# actik-retrofit.net
KiCad netlist of a schematic drawn in EAGLE
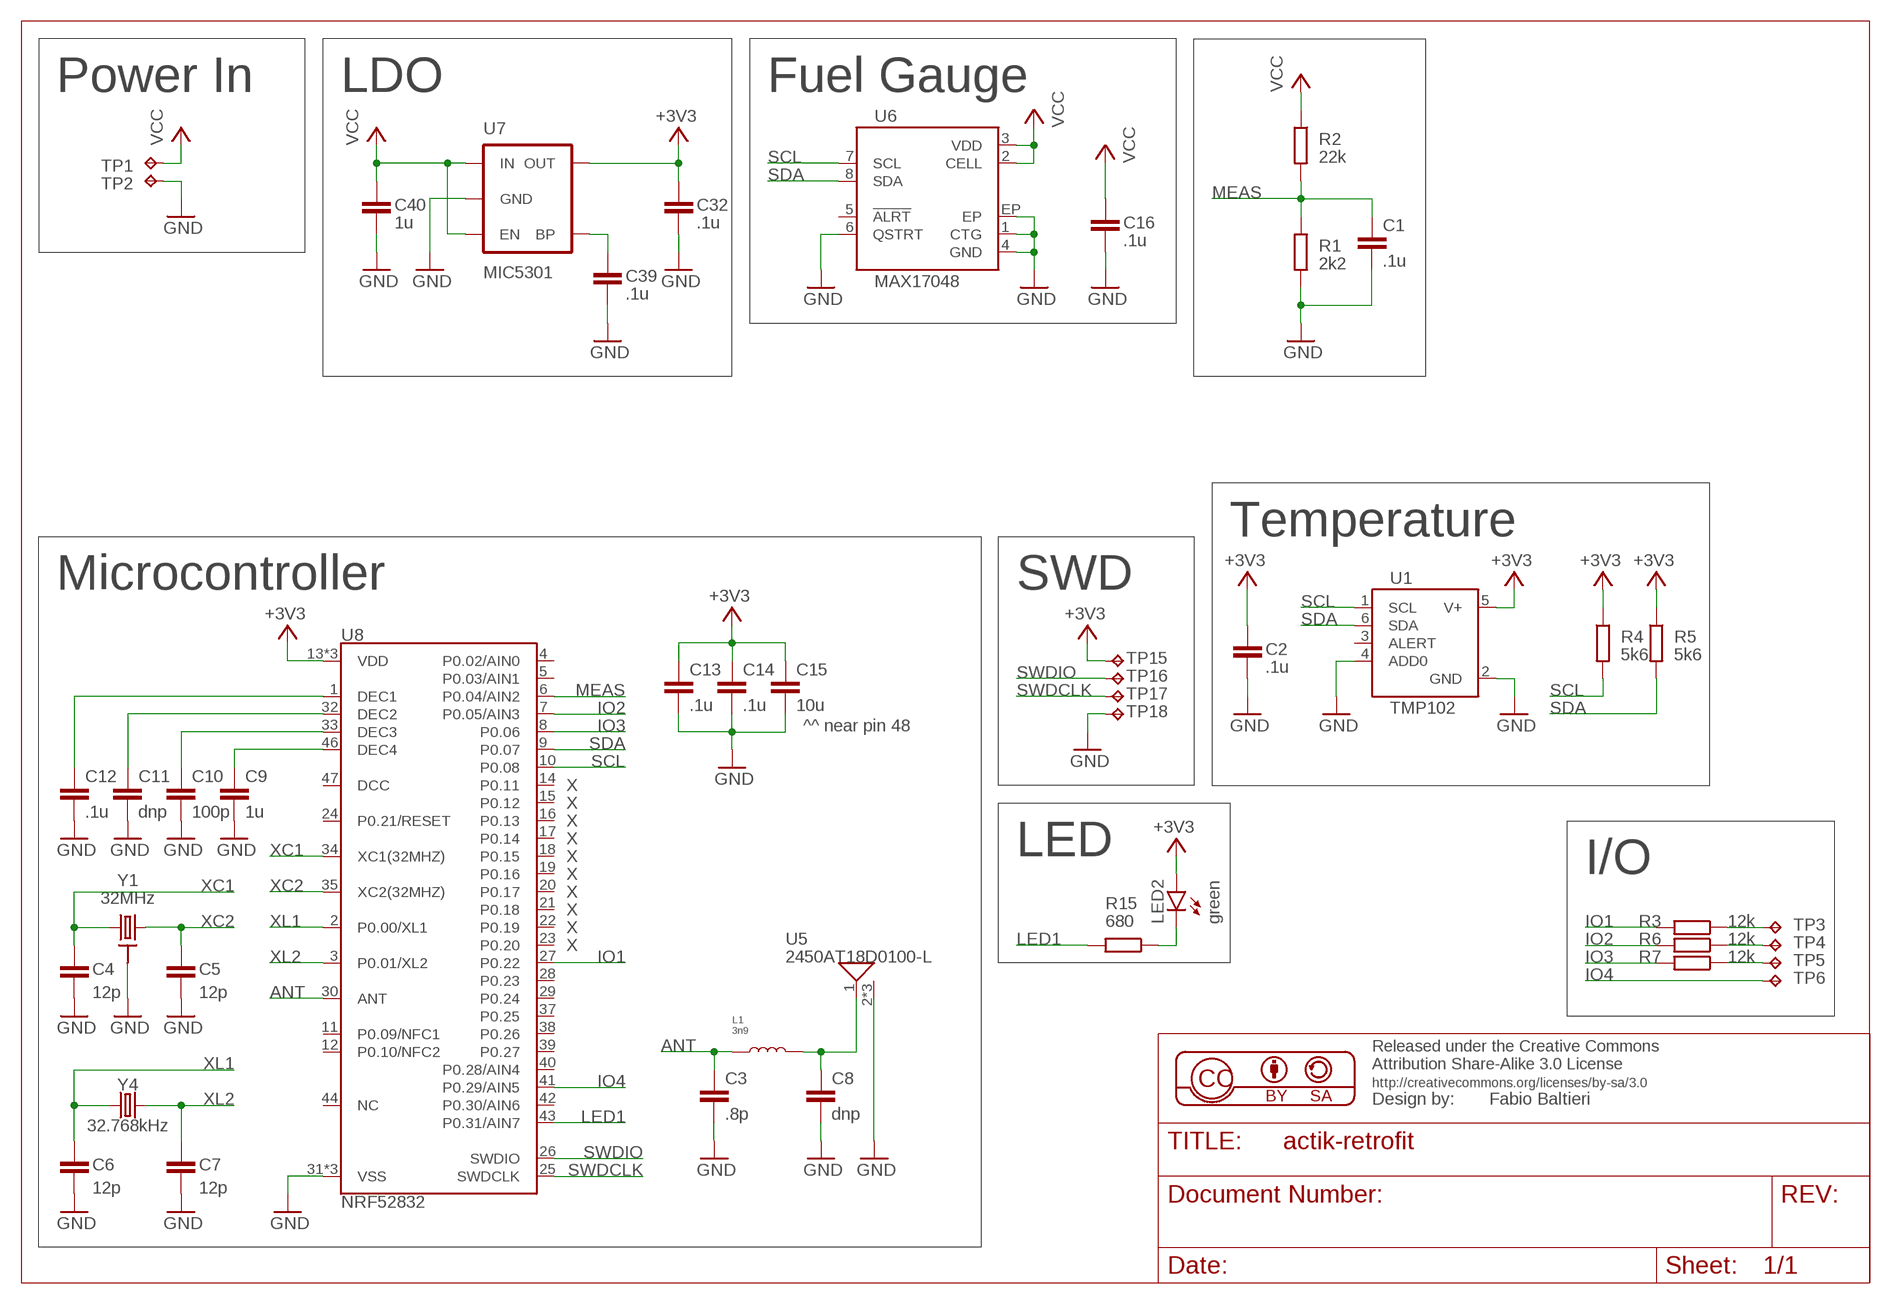
[diagram p0: schematic, sheet 1]

(export (version "E")
  (design (tool "Eeschema 10.0.6"))
  (components
    (comp (ref "C1")
      (value ".1u")
      (footprint "eagle-import:0603")
      (libsource (lib "eagle-import") (part "C0603"))
    )
    (comp (ref "C2")
      (value ".1u")
      (footprint "eagle-import:0603")
      (libsource (lib "eagle-import") (part "C0603"))
    )
    (comp (ref "C3")
      (value ".8p")
      (footprint "eagle-import:0603")
      (libsource (lib "eagle-import") (part "C0603"))
    )
    (comp (ref "C4")
      (value "12p")
      (footprint "eagle-import:0603")
      (libsource (lib "eagle-import") (part "C0603"))
    )
    (comp (ref "C5")
      (value "12p")
      (footprint "eagle-import:0603")
      (libsource (lib "eagle-import") (part "C0603"))
    )
    (comp (ref "C6")
      (value "12p")
      (footprint "eagle-import:0603")
      (libsource (lib "eagle-import") (part "C0603"))
    )
    (comp (ref "C7")
      (value "12p")
      (footprint "eagle-import:0603")
      (libsource (lib "eagle-import") (part "C0603"))
    )
    (comp (ref "C8")
      (value "dnp")
      (footprint "eagle-import:0603")
      (libsource (lib "eagle-import") (part "C0603"))
    )
    (comp (ref "C9")
      (value "1u")
      (footprint "eagle-import:0603")
      (libsource (lib "eagle-import") (part "C0603"))
    )
    (comp (ref "C10")
      (value "100p")
      (footprint "eagle-import:0603")
      (libsource (lib "eagle-import") (part "C0603"))
    )
    (comp (ref "C11")
      (value "dnp")
      (footprint "eagle-import:0603")
      (libsource (lib "eagle-import") (part "C0603"))
    )
    (comp (ref "C12")
      (value ".1u")
      (footprint "eagle-import:0603")
      (libsource (lib "eagle-import") (part "C0603"))
    )
    (comp (ref "C13")
      (value ".1u")
      (footprint "eagle-import:0603")
      (libsource (lib "eagle-import") (part "C0603"))
    )
    (comp (ref "C14")
      (value ".1u")
      (footprint "eagle-import:0603")
      (libsource (lib "eagle-import") (part "C0603"))
    )
    (comp (ref "C15")
      (value "10u")
      (footprint "eagle-import:0603")
      (libsource (lib "eagle-import") (part "C0603"))
    )
    (comp (ref "C16")
      (value ".1u")
      (footprint "eagle-import:0603")
      (libsource (lib "eagle-import") (part "C0603"))
    )
    (comp (ref "C32")
      (value ".1u")
      (footprint "eagle-import:0603")
      (libsource (lib "eagle-import") (part "C0603"))
    )
    (comp (ref "C39")
      (value ".1u")
      (footprint "eagle-import:0603")
      (libsource (lib "eagle-import") (part "C0603"))
    )
    (comp (ref "C40")
      (value "1u")
      (footprint "eagle-import:0603")
      (libsource (lib "eagle-import") (part "C0603"))
    )
    (comp (ref "L1")
      (value "3n9")
      (footprint "eagle-import:L0603")
      (libsource (lib "eagle-import") (part "INDUCTOR_0603"))
    )
    (comp (ref "LED2")
      (value "green")
      (footprint "eagle-import:SML0805")
      (libsource (lib "eagle-import") (part "LEDSML0805"))
    )
    (comp (ref "R1")
      (value "2k2")
      (footprint "eagle-import:0603")
      (libsource (lib "eagle-import") (part "R0603"))
    )
    (comp (ref "R2")
      (value "22k")
      (footprint "eagle-import:0603")
      (libsource (lib "eagle-import") (part "R0603"))
    )
    (comp (ref "R3")
      (value "12k")
      (footprint "eagle-import:0603")
      (libsource (lib "eagle-import") (part "R0603"))
    )
    (comp (ref "R4")
      (value "5k6")
      (footprint "eagle-import:0603")
      (libsource (lib "eagle-import") (part "R0603"))
    )
    (comp (ref "R5")
      (value "5k6")
      (footprint "eagle-import:0603")
      (libsource (lib "eagle-import") (part "R0603"))
    )
    (comp (ref "R6")
      (value "12k")
      (footprint "eagle-import:0603")
      (libsource (lib "eagle-import") (part "R0603"))
    )
    (comp (ref "R7")
      (value "12k")
      (footprint "eagle-import:0603")
      (libsource (lib "eagle-import") (part "R0603"))
    )
    (comp (ref "R15")
      (value "680")
      (footprint "eagle-import:0603")
      (libsource (lib "eagle-import") (part "R0603"))
    )
    (comp (ref "TP1")
      (value "TPTP10R")
      (footprint "eagle-import:TP10R")
      (libsource (lib "eagle-import") (part "TPTP10R"))
    )
    (comp (ref "TP2")
      (value "TPTP10R")
      (footprint "eagle-import:TP10R")
      (libsource (lib "eagle-import") (part "TPTP10R"))
    )
    (comp (ref "TP3")
      (value "TPTP10R")
      (footprint "eagle-import:TP10R")
      (libsource (lib "eagle-import") (part "TPTP10R"))
    )
    (comp (ref "TP4")
      (value "TPTP10R")
      (footprint "eagle-import:TP10R")
      (libsource (lib "eagle-import") (part "TPTP10R"))
    )
    (comp (ref "TP5")
      (value "TPTP10R")
      (footprint "eagle-import:TP10R")
      (libsource (lib "eagle-import") (part "TPTP10R"))
    )
    (comp (ref "TP6")
      (value "TPTP10R")
      (footprint "eagle-import:TP10R")
      (libsource (lib "eagle-import") (part "TPTP10R"))
    )
    (comp (ref "TP15")
      (value "TPTP10R")
      (footprint "eagle-import:TP10R")
      (libsource (lib "eagle-import") (part "TPTP10R"))
    )
    (comp (ref "TP16")
      (value "TPTP10R")
      (footprint "eagle-import:TP10R")
      (libsource (lib "eagle-import") (part "TPTP10R"))
    )
    (comp (ref "TP17")
      (value "TPTP10R")
      (footprint "eagle-import:TP10R")
      (libsource (lib "eagle-import") (part "TPTP10R"))
    )
    (comp (ref "TP18")
      (value "TPTP10R")
      (footprint "eagle-import:TP10R")
      (libsource (lib "eagle-import") (part "TPTP10R"))
    )
    (comp (ref "U1")
      (value "TMP102")
      (footprint "eagle-import:SOT563")
      (libsource (lib "eagle-import") (part "TMP102"))
    )
    (comp (ref "U5")
      (value "2450AT18D0100-L")
      (footprint "eagle-import:2450AT18D0100-L")
      (libsource (lib "eagle-import") (part "2450AT18D0100-L"))
    )
    (comp (ref "U6")
      (value "MAX17048")
      (footprint "eagle-import:TDFN8L")
      (libsource (lib "eagle-import") (part "MAX17048"))
    )
    (comp (ref "U7")
      (value "MIC5301")
      (footprint "eagle-import:SOT23-5")
      (libsource (lib "eagle-import") (part "V_REG_LDOSMD"))
    )
    (comp (ref "U8")
      (value "NRF52832")
      (footprint "eagle-import:QFN48-6X6MM")
      (libsource (lib "eagle-import") (part "NRF52832"))
    )
    (comp (ref "Y1")
      (value "32MHz")
      (footprint "eagle-import:XTAL-2X1.6")
      (libsource (lib "eagle-import") (part "XTAL-GND-2X1.6"))
    )
    (comp (ref "Y4")
      (value "32.768kHz")
      (footprint "eagle-import:CRYSTAL-SMD-3.2X1.5MM")
      (libsource (lib "eagle-import") (part "CRYSTAL-32.768KHZSMD-3.2X1.5"))
    )
  )
  (nets
    (net (code "1") (name "+3V3") (class "Default")
      (node (ref "C13") (pin "1") (pinfunction "1_1") (pintype "passive"))
      (node (ref "C14") (pin "1") (pinfunction "1_1") (pintype "passive"))
      (node (ref "C15") (pin "1") (pinfunction "1_1") (pintype "passive"))
      (node (ref "C2") (pin "1") (pinfunction "1_1") (pintype "passive"))
      (node (ref "C32") (pin "1") (pinfunction "1_1") (pintype "passive"))
      (node (ref "LED2") (pin "A") (pinfunction "A_A") (pintype "passive"))
      (node (ref "R4") (pin "1") (pinfunction "1_1") (pintype "passive"))
      (node (ref "R5") (pin "1") (pinfunction "1_1") (pintype "passive"))
      (node (ref "TP15") (pin "TP") (pinfunction "TP_TP") (pintype "input"))
      (node (ref "U1") (pin "5") (pinfunction "V+_5") (pintype "bidirectional"))
      (node (ref "U7") (pin "5") (pinfunction "OUT_5") (pintype "passive"))
      (node (ref "U8") (pin "13") (pinfunction "VDD_13") (pintype "bidirectional"))
      (node (ref "U8") (pin "36") (pinfunction "VDD_36") (pintype "bidirectional"))
      (node (ref "U8") (pin "48") (pinfunction "VDD_48") (pintype "bidirectional"))
    )
    (net (code "2") (name "/ANT") (class "Default")
      (node (ref "C3") (pin "1") (pinfunction "1_1") (pintype "passive"))
      (node (ref "L1") (pin "P$1") (pinfunction "P$1_P$1") (pintype "passive"))
      (node (ref "U8") (pin "30") (pinfunction "ANT_30") (pintype "bidirectional"))
    )
    (net (code "3") (name "/IO1") (class "Default")
      (node (ref "R3") (pin "2") (pinfunction "2_2") (pintype "passive"))
      (node (ref "U8") (pin "27") (pinfunction "P0.22_27") (pintype "bidirectional"))
    )
    (net (code "4") (name "/IO2") (class "Default")
      (node (ref "R6") (pin "2") (pinfunction "2_2") (pintype "passive"))
      (node (ref "U8") (pin "7") (pinfunction "P0.05/AIN3_7") (pintype "bidirectional"))
    )
    (net (code "5") (name "/IO3") (class "Default")
      (node (ref "R7") (pin "2") (pinfunction "2_2") (pintype "passive"))
      (node (ref "U8") (pin "8") (pinfunction "P0.06_8") (pintype "bidirectional"))
    )
    (net (code "6") (name "/IO4") (class "Default")
      (node (ref "TP6") (pin "TP") (pinfunction "TP_TP") (pintype "input"))
      (node (ref "U8") (pin "41") (pinfunction "P0.29/AIN5_41") (pintype "bidirectional"))
    )
    (net (code "7") (name "/LED1") (class "Default")
      (node (ref "R15") (pin "2") (pinfunction "2_2") (pintype "passive"))
      (node (ref "U8") (pin "43") (pinfunction "P0.31/AIN7_43") (pintype "bidirectional"))
    )
    (net (code "8") (name "/MEAS") (class "Default")
      (node (ref "C1") (pin "1") (pinfunction "1_1") (pintype "passive"))
      (node (ref "R1") (pin "1") (pinfunction "1_1") (pintype "passive"))
      (node (ref "R2") (pin "2") (pinfunction "2_2") (pintype "passive"))
      (node (ref "U8") (pin "6") (pinfunction "P0.04/AIN2_6") (pintype "bidirectional"))
    )
    (net (code "9") (name "/SCL") (class "Default")
      (node (ref "R4") (pin "2") (pinfunction "2_2") (pintype "passive"))
      (node (ref "U1") (pin "1") (pinfunction "SCL_1") (pintype "bidirectional"))
      (node (ref "U6") (pin "7") (pinfunction "SCL_7") (pintype "bidirectional"))
      (node (ref "U8") (pin "10") (pinfunction "P0.08_10") (pintype "bidirectional"))
    )
    (net (code "10") (name "/SDA") (class "Default")
      (node (ref "R5") (pin "2") (pinfunction "2_2") (pintype "passive"))
      (node (ref "U1") (pin "6") (pinfunction "SDA_6") (pintype "bidirectional"))
      (node (ref "U6") (pin "8") (pinfunction "SDA_8") (pintype "bidirectional"))
      (node (ref "U8") (pin "9") (pinfunction "P0.07_9") (pintype "bidirectional"))
    )
    (net (code "11") (name "/SWDCLK") (class "Default")
      (node (ref "TP17") (pin "TP") (pinfunction "TP_TP") (pintype "input"))
      (node (ref "U8") (pin "25") (pinfunction "SWDCLK_25") (pintype "bidirectional"))
    )
    (net (code "12") (name "/SWDIO") (class "Default")
      (node (ref "TP16") (pin "TP") (pinfunction "TP_TP") (pintype "input"))
      (node (ref "U8") (pin "26") (pinfunction "SWDIO_26") (pintype "bidirectional"))
    )
    (net (code "13") (name "/XC1") (class "Default")
      (node (ref "C4") (pin "1") (pinfunction "1_1") (pintype "passive"))
      (node (ref "U8") (pin "34") (pinfunction "XC1(32MHZ)_34") (pintype "bidirectional"))
      (node (ref "Y1") (pin "1") (pinfunction "1_1") (pintype "passive"))
    )
    (net (code "14") (name "/XC2") (class "Default")
      (node (ref "C5") (pin "1") (pinfunction "1_1") (pintype "passive"))
      (node (ref "U8") (pin "35") (pinfunction "XC2(32MHZ)_35") (pintype "bidirectional"))
      (node (ref "Y1") (pin "3") (pinfunction "2_3") (pintype "passive"))
    )
    (net (code "15") (name "/XL1") (class "Default")
      (node (ref "C6") (pin "1") (pinfunction "1_1") (pintype "passive"))
      (node (ref "U8") (pin "2") (pinfunction "P0.00/XL1_2") (pintype "bidirectional"))
      (node (ref "Y4") (pin "P$1") (pinfunction "1_P$1") (pintype "passive"))
    )
    (net (code "16") (name "/XL2") (class "Default")
      (node (ref "C7") (pin "1") (pinfunction "1_1") (pintype "passive"))
      (node (ref "U8") (pin "3") (pinfunction "P0.01/XL2_3") (pintype "bidirectional"))
      (node (ref "Y4") (pin "P$2") (pinfunction "2_P$2") (pintype "passive"))
    )
    (net (code "17") (name "GND") (class "Default")
      (node (ref "C1") (pin "2") (pinfunction "2_2") (pintype "passive"))
      (node (ref "C10") (pin "2") (pinfunction "2_2") (pintype "passive"))
      (node (ref "C11") (pin "2") (pinfunction "2_2") (pintype "passive"))
      (node (ref "C12") (pin "2") (pinfunction "2_2") (pintype "passive"))
      (node (ref "C13") (pin "2") (pinfunction "2_2") (pintype "passive"))
      (node (ref "C14") (pin "2") (pinfunction "2_2") (pintype "passive"))
      (node (ref "C15") (pin "2") (pinfunction "2_2") (pintype "passive"))
      (node (ref "C16") (pin "2") (pinfunction "2_2") (pintype "passive"))
      (node (ref "C2") (pin "2") (pinfunction "2_2") (pintype "passive"))
      (node (ref "C3") (pin "2") (pinfunction "2_2") (pintype "passive"))
      (node (ref "C32") (pin "2") (pinfunction "2_2") (pintype "passive"))
      (node (ref "C39") (pin "2") (pinfunction "2_2") (pintype "passive"))
      (node (ref "C4") (pin "2") (pinfunction "2_2") (pintype "passive"))
      (node (ref "C40") (pin "2") (pinfunction "2_2") (pintype "passive"))
      (node (ref "C5") (pin "2") (pinfunction "2_2") (pintype "passive"))
      (node (ref "C6") (pin "2") (pinfunction "2_2") (pintype "passive"))
      (node (ref "C7") (pin "2") (pinfunction "2_2") (pintype "passive"))
      (node (ref "C8") (pin "2") (pinfunction "2_2") (pintype "passive"))
      (node (ref "C9") (pin "2") (pinfunction "2_2") (pintype "passive"))
      (node (ref "R1") (pin "2") (pinfunction "2_2") (pintype "passive"))
      (node (ref "TP18") (pin "TP") (pinfunction "TP_TP") (pintype "input"))
      (node (ref "TP2") (pin "TP") (pinfunction "TP_TP") (pintype "input"))
      (node (ref "U1") (pin "2") (pinfunction "GND_2") (pintype "bidirectional"))
      (node (ref "U1") (pin "4") (pinfunction "ADD0_4") (pintype "bidirectional"))
      (node (ref "U5") (pin "2") (pinfunction "GND_2") (pintype "bidirectional"))
      (node (ref "U5") (pin "3") (pinfunction "GND_3") (pintype "bidirectional"))
      (node (ref "U5") (pin "4") (pinfunction "GND_4") (pintype "bidirectional"))
      (node (ref "U6") (pin "1") (pinfunction "CTG_1") (pintype "bidirectional"))
      (node (ref "U6") (pin "4") (pinfunction "GND_4") (pintype "bidirectional"))
      (node (ref "U6") (pin "6") (pinfunction "QSTRT_6") (pintype "bidirectional"))
      (node (ref "U6") (pin "EP") (pinfunction "EP_EP") (pintype "bidirectional"))
      (node (ref "U7") (pin "2") (pinfunction "GND_2") (pintype "input"))
      (node (ref "U8") (pin "31") (pinfunction "VSS_31") (pintype "bidirectional"))
      (node (ref "U8") (pin "45") (pinfunction "VSS_45") (pintype "bidirectional"))
      (node (ref "U8") (pin "EP") (pinfunction "VSS_EP") (pintype "bidirectional"))
      (node (ref "Y1") (pin "2") (pinfunction "GND_2") (pintype "passive"))
      (node (ref "Y1") (pin "4") (pinfunction "GND_4") (pintype "passive"))
    )
    (net (code "18") (name "Net-(LED2-PadC)") (class "Default")
      (node (ref "LED2") (pin "C") (pinfunction "C_C") (pintype "passive"))
      (node (ref "R15") (pin "1") (pinfunction "1_1") (pintype "passive"))
    )
    (net (code "19") (name "Net-(R3-Pad1)") (class "Default")
      (node (ref "R3") (pin "1") (pinfunction "1_1") (pintype "passive"))
      (node (ref "TP3") (pin "TP") (pinfunction "TP_TP") (pintype "input"))
    )
    (net (code "20") (name "Net-(R6-Pad1)") (class "Default")
      (node (ref "R6") (pin "1") (pinfunction "1_1") (pintype "passive"))
      (node (ref "TP4") (pin "TP") (pinfunction "TP_TP") (pintype "input"))
    )
    (net (code "21") (name "Net-(R7-Pad1)") (class "Default")
      (node (ref "R7") (pin "1") (pinfunction "1_1") (pintype "passive"))
      (node (ref "TP5") (pin "TP") (pinfunction "TP_TP") (pintype "input"))
    )
    (net (code "22") (name "Net-(U5-FEED)") (class "Default")
      (node (ref "C8") (pin "1") (pinfunction "1_1") (pintype "passive"))
      (node (ref "L1") (pin "P$2") (pinfunction "P$2_P$2") (pintype "passive"))
      (node (ref "U5") (pin "1") (pinfunction "FEED_1") (pintype "bidirectional"))
    )
    (net (code "23") (name "Net-(U7-BP)") (class "Default")
      (node (ref "C39") (pin "1") (pinfunction "1_1") (pintype "passive"))
      (node (ref "U7") (pin "4") (pinfunction "BP_4") (pintype "input"))
    )
    (net (code "24") (name "Net-(U8-DEC1)") (class "Default")
      (node (ref "C12") (pin "1") (pinfunction "1_1") (pintype "passive"))
      (node (ref "U8") (pin "1") (pinfunction "DEC1_1") (pintype "bidirectional"))
    )
    (net (code "25") (name "Net-(U8-DEC2)") (class "Default")
      (node (ref "C11") (pin "1") (pinfunction "1_1") (pintype "passive"))
      (node (ref "U8") (pin "32") (pinfunction "DEC2_32") (pintype "bidirectional"))
    )
    (net (code "26") (name "Net-(U8-DEC3)") (class "Default")
      (node (ref "C10") (pin "1") (pinfunction "1_1") (pintype "passive"))
      (node (ref "U8") (pin "33") (pinfunction "DEC3_33") (pintype "bidirectional"))
    )
    (net (code "27") (name "Net-(U8-DEC4)") (class "Default")
      (node (ref "C9") (pin "1") (pinfunction "1_1") (pintype "passive"))
      (node (ref "U8") (pin "46") (pinfunction "DEC4_46") (pintype "bidirectional"))
    )
    (net (code "28") (name "VCC") (class "Default")
      (node (ref "C16") (pin "1") (pinfunction "1_1") (pintype "passive"))
      (node (ref "C40") (pin "1") (pinfunction "1_1") (pintype "passive"))
      (node (ref "R2") (pin "1") (pinfunction "1_1") (pintype "passive"))
      (node (ref "TP1") (pin "TP") (pinfunction "TP_TP") (pintype "input"))
      (node (ref "U6") (pin "2") (pinfunction "CELL_2") (pintype "bidirectional"))
      (node (ref "U6") (pin "3") (pinfunction "VDD_3") (pintype "bidirectional"))
      (node (ref "U7") (pin "1") (pinfunction "IN_1") (pintype "input"))
      (node (ref "U7") (pin "3") (pinfunction "EN_3") (pintype "input"))
    )
    (net (code "29") (name "unconnected-(U1-ALERT-Pad3)") (class "Default")
      (node (ref "U1") (pin "3") (pinfunction "ALERT_3") (pintype "bidirectional"))
    )
    (net (code "30") (name "unconnected-(U6-~{ALRT}-Pad5)") (class "Default")
      (node (ref "U6") (pin "5") (pinfunction "~{ALRT}_5") (pintype "bidirectional"))
    )
    (net (code "31") (name "unconnected-(U8-DCC-Pad47)") (class "Default")
      (node (ref "U8") (pin "47") (pinfunction "DCC_47") (pintype "bidirectional"))
    )
    (net (code "32") (name "unconnected-(U8-NC-Pad44)") (class "Default")
      (node (ref "U8") (pin "44") (pinfunction "NC_44") (pintype "bidirectional"))
    )
    (net (code "33") (name "unconnected-(U8-P0.02{slash}AIN0-Pad4)") (class "Default")
      (node (ref "U8") (pin "4") (pinfunction "P0.02/AIN0_4") (pintype "bidirectional"))
    )
    (net (code "34") (name "unconnected-(U8-P0.03{slash}AIN1-Pad5)") (class "Default")
      (node (ref "U8") (pin "5") (pinfunction "P0.03/AIN1_5") (pintype "bidirectional"))
    )
    (net (code "35") (name "unconnected-(U8-P0.09{slash}NFC1-Pad11)") (class "Default")
      (node (ref "U8") (pin "11") (pinfunction "P0.09/NFC1_11") (pintype "bidirectional"))
    )
    (net (code "36") (name "unconnected-(U8-P0.10{slash}NFC2-Pad12)") (class "Default")
      (node (ref "U8") (pin "12") (pinfunction "P0.10/NFC2_12") (pintype "bidirectional"))
    )
    (net (code "37") (name "unconnected-(U8-P0.11-Pad14)") (class "Default")
      (node (ref "U8") (pin "14") (pinfunction "P0.11_14") (pintype "bidirectional"))
    )
    (net (code "38") (name "unconnected-(U8-P0.12-Pad15)") (class "Default")
      (node (ref "U8") (pin "15") (pinfunction "P0.12_15") (pintype "bidirectional"))
    )
    (net (code "39") (name "unconnected-(U8-P0.13-Pad16)") (class "Default")
      (node (ref "U8") (pin "16") (pinfunction "P0.13_16") (pintype "bidirectional"))
    )
    (net (code "40") (name "unconnected-(U8-P0.14-Pad17)") (class "Default")
      (node (ref "U8") (pin "17") (pinfunction "P0.14_17") (pintype "bidirectional"))
    )
    (net (code "41") (name "unconnected-(U8-P0.15-Pad18)") (class "Default")
      (node (ref "U8") (pin "18") (pinfunction "P0.15_18") (pintype "bidirectional"))
    )
    (net (code "42") (name "unconnected-(U8-P0.16-Pad19)") (class "Default")
      (node (ref "U8") (pin "19") (pinfunction "P0.16_19") (pintype "bidirectional"))
    )
    (net (code "43") (name "unconnected-(U8-P0.17-Pad20)") (class "Default")
      (node (ref "U8") (pin "20") (pinfunction "P0.17_20") (pintype "bidirectional"))
    )
    (net (code "44") (name "unconnected-(U8-P0.18-Pad21)") (class "Default")
      (node (ref "U8") (pin "21") (pinfunction "P0.18_21") (pintype "bidirectional"))
    )
    (net (code "45") (name "unconnected-(U8-P0.19-Pad22)") (class "Default")
      (node (ref "U8") (pin "22") (pinfunction "P0.19_22") (pintype "bidirectional"))
    )
    (net (code "46") (name "unconnected-(U8-P0.20-Pad23)") (class "Default")
      (node (ref "U8") (pin "23") (pinfunction "P0.20_23") (pintype "bidirectional"))
    )
    (net (code "47") (name "unconnected-(U8-P0.21{slash}RESET-Pad24)") (class "Default")
      (node (ref "U8") (pin "24") (pinfunction "P0.21/RESET_24") (pintype "bidirectional"))
    )
    (net (code "48") (name "unconnected-(U8-P0.23-Pad28)") (class "Default")
      (node (ref "U8") (pin "28") (pinfunction "P0.23_28") (pintype "bidirectional"))
    )
    (net (code "49") (name "unconnected-(U8-P0.24-Pad29)") (class "Default")
      (node (ref "U8") (pin "29") (pinfunction "P0.24_29") (pintype "bidirectional"))
    )
    (net (code "50") (name "unconnected-(U8-P0.25-Pad37)") (class "Default")
      (node (ref "U8") (pin "37") (pinfunction "P0.25_37") (pintype "bidirectional"))
    )
    (net (code "51") (name "unconnected-(U8-P0.26-Pad38)") (class "Default")
      (node (ref "U8") (pin "38") (pinfunction "P0.26_38") (pintype "bidirectional"))
    )
    (net (code "52") (name "unconnected-(U8-P0.27-Pad39)") (class "Default")
      (node (ref "U8") (pin "39") (pinfunction "P0.27_39") (pintype "bidirectional"))
    )
    (net (code "53") (name "unconnected-(U8-P0.28{slash}AIN4-Pad40)") (class "Default")
      (node (ref "U8") (pin "40") (pinfunction "P0.28/AIN4_40") (pintype "bidirectional"))
    )
    (net (code "54") (name "unconnected-(U8-P0.30{slash}AIN6-Pad42)") (class "Default")
      (node (ref "U8") (pin "42") (pinfunction "P0.30/AIN6_42") (pintype "bidirectional"))
    )
  )
)
